# ESP32_D1_Mini_Breakout.net
KiCad netlist of a schematic drawn in EAGLE
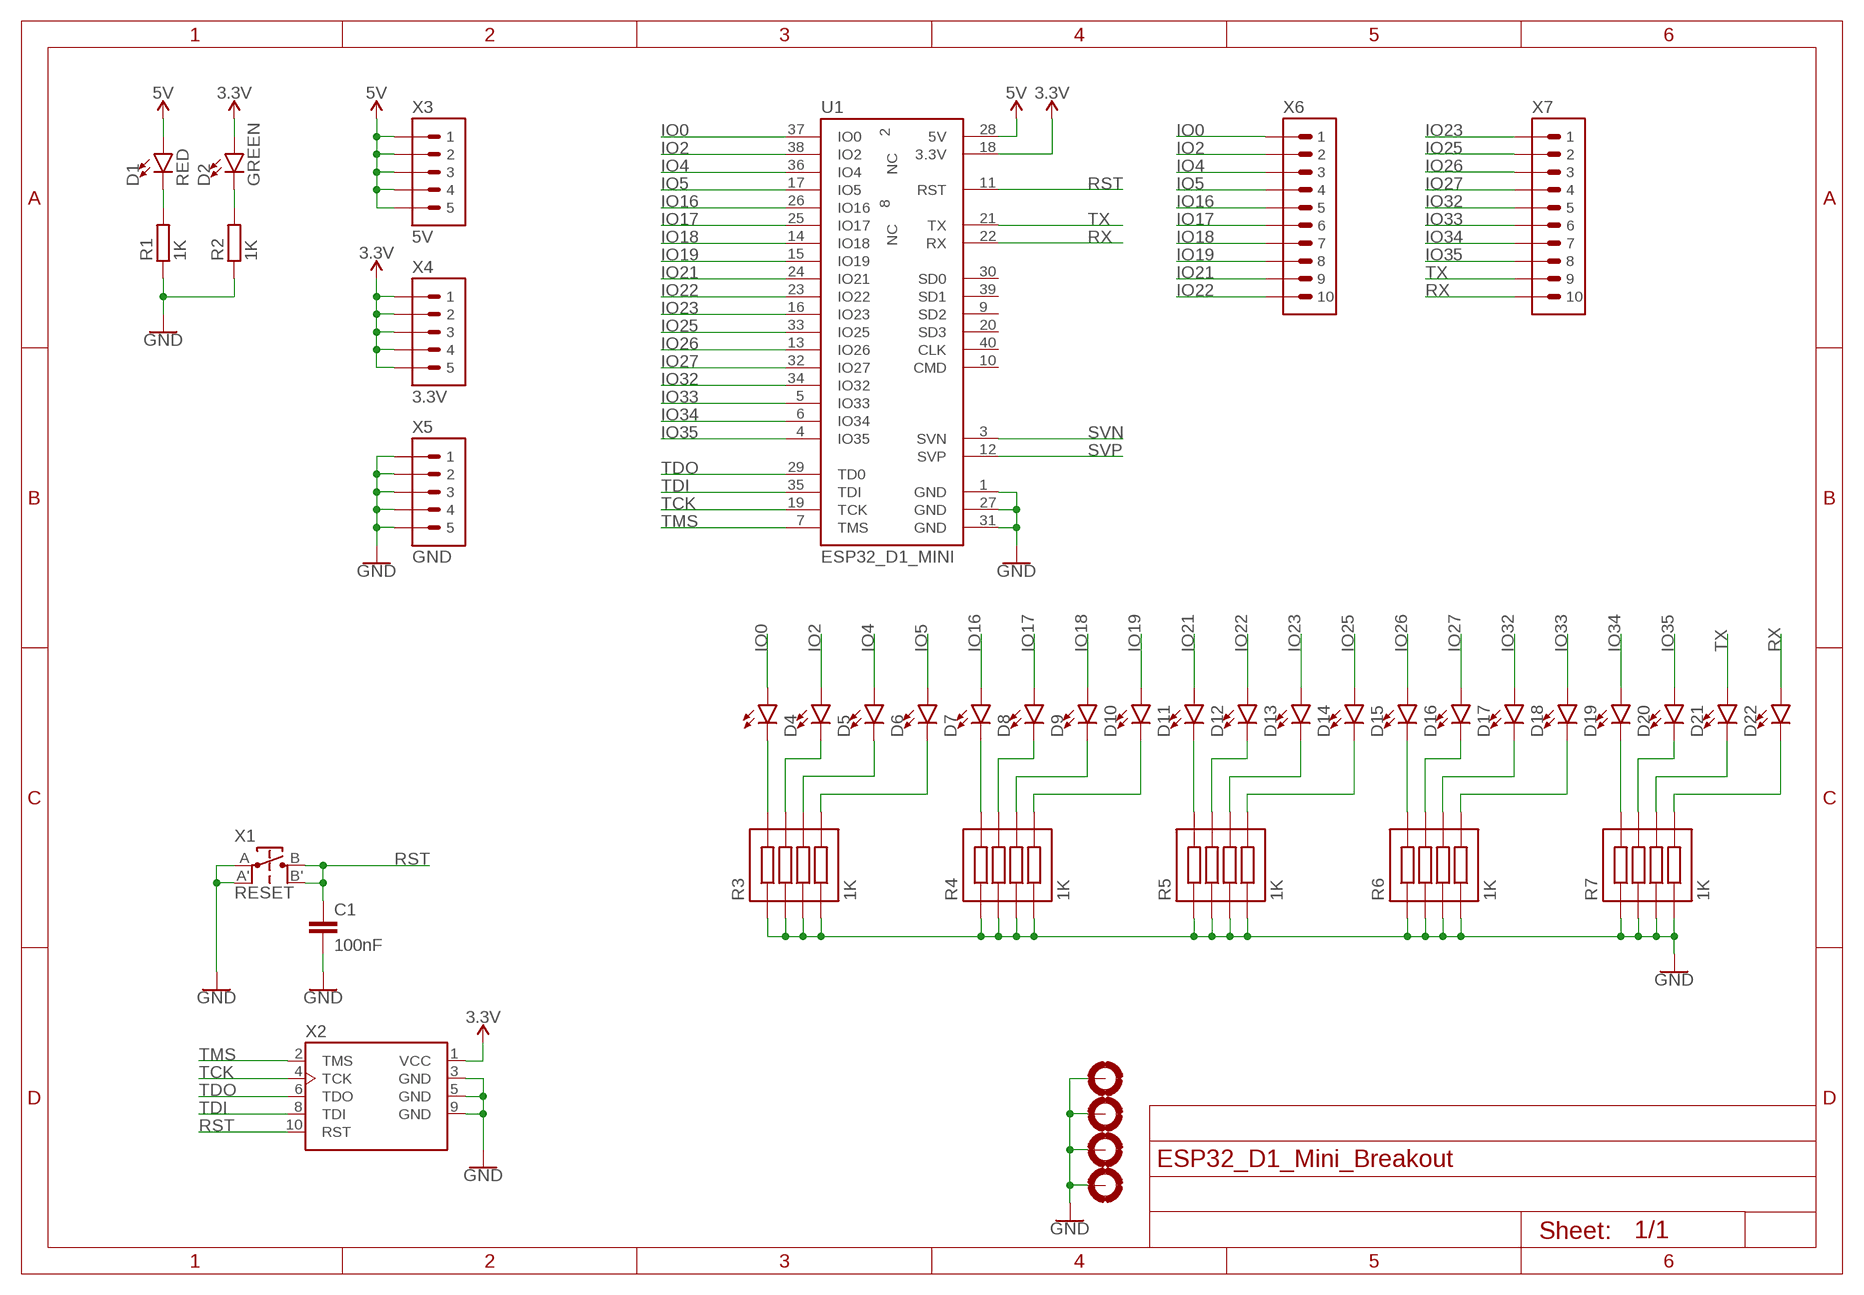
[diagram p0: schematic, sheet 1]

(export (version "E")
  (design (tool "Eeschema 10.0.6"))
  (components
    (comp (ref "C1")
      (value "100nF")
      (footprint "eagle-import:C0603")
      (libsource (lib "eagle-import") (part "CAPC0603"))
    )
    (comp (ref "D1")
      (value "RED")
      (footprint "eagle-import:LED0603")
      (libsource (lib "eagle-import") (part "LED0603"))
    )
    (comp (ref "D2")
      (value "GREEN")
      (footprint "eagle-import:LED0603")
      (libsource (lib "eagle-import") (part "LED0603"))
    )
    (comp (ref "D3")
      (value "LED0603")
      (footprint "eagle-import:LED0603")
      (libsource (lib "eagle-import") (part "LED0603"))
    )
    (comp (ref "D4")
      (value "LED0603")
      (footprint "eagle-import:LED0603")
      (libsource (lib "eagle-import") (part "LED0603"))
    )
    (comp (ref "D5")
      (value "LED0603")
      (footprint "eagle-import:LED0603")
      (libsource (lib "eagle-import") (part "LED0603"))
    )
    (comp (ref "D6")
      (value "LED0603")
      (footprint "eagle-import:LED0603")
      (libsource (lib "eagle-import") (part "LED0603"))
    )
    (comp (ref "D7")
      (value "LED0603")
      (footprint "eagle-import:LED0603")
      (libsource (lib "eagle-import") (part "LED0603"))
    )
    (comp (ref "D8")
      (value "LED0603")
      (footprint "eagle-import:LED0603")
      (libsource (lib "eagle-import") (part "LED0603"))
    )
    (comp (ref "D9")
      (value "LED0603")
      (footprint "eagle-import:LED0603")
      (libsource (lib "eagle-import") (part "LED0603"))
    )
    (comp (ref "D10")
      (value "LED0603")
      (footprint "eagle-import:LED0603")
      (libsource (lib "eagle-import") (part "LED0603"))
    )
    (comp (ref "D11")
      (value "LED0603")
      (footprint "eagle-import:LED0603")
      (libsource (lib "eagle-import") (part "LED0603"))
    )
    (comp (ref "D12")
      (value "LED0603")
      (footprint "eagle-import:LED0603")
      (libsource (lib "eagle-import") (part "LED0603"))
    )
    (comp (ref "D13")
      (value "LED0603")
      (footprint "eagle-import:LED0603")
      (libsource (lib "eagle-import") (part "LED0603"))
    )
    (comp (ref "D14")
      (value "LED0603")
      (footprint "eagle-import:LED0603")
      (libsource (lib "eagle-import") (part "LED0603"))
    )
    (comp (ref "D15")
      (value "LED0603")
      (footprint "eagle-import:LED0603")
      (libsource (lib "eagle-import") (part "LED0603"))
    )
    (comp (ref "D16")
      (value "LED0603")
      (footprint "eagle-import:LED0603")
      (libsource (lib "eagle-import") (part "LED0603"))
    )
    (comp (ref "D17")
      (value "LED0603")
      (footprint "eagle-import:LED0603")
      (libsource (lib "eagle-import") (part "LED0603"))
    )
    (comp (ref "D18")
      (value "LED0603")
      (footprint "eagle-import:LED0603")
      (libsource (lib "eagle-import") (part "LED0603"))
    )
    (comp (ref "D19")
      (value "LED0603")
      (footprint "eagle-import:LED0603")
      (libsource (lib "eagle-import") (part "LED0603"))
    )
    (comp (ref "D20")
      (value "LED0603")
      (footprint "eagle-import:LED0603")
      (libsource (lib "eagle-import") (part "LED0603"))
    )
    (comp (ref "D21")
      (value "LED0603")
      (footprint "eagle-import:LED0603")
      (libsource (lib "eagle-import") (part "LED0603"))
    )
    (comp (ref "D22")
      (value "LED0603")
      (footprint "eagle-import:LED0603")
      (libsource (lib "eagle-import") (part "LED0603"))
    )
    (comp (ref "H1")
      (value "MOUNTHOLE-PAD3.2")
      (footprint "eagle-import:3.2-PAD")
      (libsource (lib "eagle-import") (part "MOUNTHOLE-PAD3.2"))
    )
    (comp (ref "H2")
      (value "MOUNTHOLE-PAD3.2")
      (footprint "eagle-import:3.2-PAD")
      (libsource (lib "eagle-import") (part "MOUNTHOLE-PAD3.2"))
    )
    (comp (ref "H3")
      (value "MOUNTHOLE-PAD3.2")
      (footprint "eagle-import:3.2-PAD")
      (libsource (lib "eagle-import") (part "MOUNTHOLE-PAD3.2"))
    )
    (comp (ref "H4")
      (value "MOUNTHOLE-PAD3.2")
      (footprint "eagle-import:3.2-PAD")
      (libsource (lib "eagle-import") (part "MOUNTHOLE-PAD3.2"))
    )
    (comp (ref "R1")
      (value "1K")
      (footprint "eagle-import:R0603")
      (libsource (lib "eagle-import") (part "RESISTOR0603"))
    )
    (comp (ref "R2")
      (value "1K")
      (footprint "eagle-import:R0603")
      (libsource (lib "eagle-import") (part "RESISTOR0603"))
    )
    (comp (ref "R3")
      (value "1K")
      (footprint "eagle-import:RX4_1206")
      (libsource (lib "eagle-import") (part "RESISTOR-ARRAY-X41206"))
    )
    (comp (ref "R4")
      (value "1K")
      (footprint "eagle-import:RX4_1206")
      (libsource (lib "eagle-import") (part "RESISTOR-ARRAY-X41206"))
    )
    (comp (ref "R5")
      (value "1K")
      (footprint "eagle-import:RX4_1206")
      (libsource (lib "eagle-import") (part "RESISTOR-ARRAY-X41206"))
    )
    (comp (ref "R6")
      (value "1K")
      (footprint "eagle-import:RX4_1206")
      (libsource (lib "eagle-import") (part "RESISTOR-ARRAY-X41206"))
    )
    (comp (ref "R7")
      (value "1K")
      (footprint "eagle-import:RX4_1206")
      (libsource (lib "eagle-import") (part "RESISTOR-ARRAY-X41206"))
    )
    (comp (ref "U1")
      (value "ESP32_D1_MINI")
      (footprint "eagle-import:WEMOS_ESP32_D1_MINI")
      (libsource (lib "eagle-import") (part "WEMOS_ESP32_D1_MINI"))
    )
    (comp (ref "X1")
      (value "RESET")
      (footprint "eagle-import:TACT-SWITCH-EVQ")
      (libsource (lib "eagle-import") (part "TACT-SWITCHEVQ"))
    )
    (comp (ref "X2")
      (value "ESP32-JTAGTH")
      (footprint "eagle-import:2X05-1.27-SWD")
      (libsource (lib "eagle-import") (part "ESP32-JTAGTH"))
    )
    (comp (ref "X3")
      (value "5V")
      (footprint "eagle-import:1X05-2.54")
      (libsource (lib "eagle-import") (part "HEADER-1X05-2.54"))
    )
    (comp (ref "X4")
      (value "3.3V")
      (footprint "eagle-import:1X05-2.54")
      (libsource (lib "eagle-import") (part "HEADER-1X05-2.54"))
    )
    (comp (ref "X5")
      (value "GND")
      (footprint "eagle-import:1X05-2.54")
      (libsource (lib "eagle-import") (part "HEADER-1X05-2.54"))
    )
    (comp (ref "X6")
      (value "HEADER-1X10-2.54")
      (footprint "eagle-import:1X10-2.54")
      (libsource (lib "eagle-import") (part "HEADER-1X10-2.54"))
    )
    (comp (ref "X7")
      (value "HEADER-1X10-2.54")
      (footprint "eagle-import:1X10-2.54")
      (libsource (lib "eagle-import") (part "HEADER-1X10-2.54"))
    )
  )
  (nets
    (net (code "1") (name "/IO0") (class "Default")
      (node (ref "D3") (pin "A") (pinfunction "A_A") (pintype "passive"))
      (node (ref "U1") (pin "37") (pinfunction "IO0_37") (pintype "bidirectional"))
      (node (ref "X6") (pin "1") (pinfunction "1_1") (pintype "passive"))
    )
    (net (code "2") (name "/IO2") (class "Default")
      (node (ref "D4") (pin "A") (pinfunction "A_A") (pintype "passive"))
      (node (ref "U1") (pin "38") (pinfunction "IO2_38") (pintype "bidirectional"))
      (node (ref "X6") (pin "2") (pinfunction "2_2") (pintype "passive"))
    )
    (net (code "3") (name "/IO4") (class "Default")
      (node (ref "D5") (pin "A") (pinfunction "A_A") (pintype "passive"))
      (node (ref "U1") (pin "36") (pinfunction "IO4_36") (pintype "bidirectional"))
      (node (ref "X6") (pin "3") (pinfunction "3_3") (pintype "passive"))
    )
    (net (code "4") (name "/IO5") (class "Default")
      (node (ref "D6") (pin "A") (pinfunction "A_A") (pintype "passive"))
      (node (ref "U1") (pin "17") (pinfunction "IO5_17") (pintype "bidirectional"))
      (node (ref "X6") (pin "4") (pinfunction "4_4") (pintype "passive"))
    )
    (net (code "5") (name "/IO16") (class "Default")
      (node (ref "D7") (pin "A") (pinfunction "A_A") (pintype "passive"))
      (node (ref "U1") (pin "26") (pinfunction "IO16_26") (pintype "bidirectional"))
      (node (ref "X6") (pin "5") (pinfunction "5_5") (pintype "passive"))
    )
    (net (code "6") (name "/IO17") (class "Default")
      (node (ref "D8") (pin "A") (pinfunction "A_A") (pintype "passive"))
      (node (ref "U1") (pin "25") (pinfunction "IO17_25") (pintype "bidirectional"))
      (node (ref "X6") (pin "6") (pinfunction "6_6") (pintype "passive"))
    )
    (net (code "7") (name "/IO18") (class "Default")
      (node (ref "D9") (pin "A") (pinfunction "A_A") (pintype "passive"))
      (node (ref "U1") (pin "14") (pinfunction "IO18_14") (pintype "bidirectional"))
      (node (ref "X6") (pin "7") (pinfunction "7_7") (pintype "passive"))
    )
    (net (code "8") (name "/IO19") (class "Default")
      (node (ref "D10") (pin "A") (pinfunction "A_A") (pintype "passive"))
      (node (ref "U1") (pin "15") (pinfunction "IO19_15") (pintype "bidirectional"))
      (node (ref "X6") (pin "8") (pinfunction "8_8") (pintype "bidirectional"))
    )
    (net (code "9") (name "/IO21") (class "Default")
      (node (ref "D11") (pin "A") (pinfunction "A_A") (pintype "passive"))
      (node (ref "U1") (pin "24") (pinfunction "IO21_24") (pintype "bidirectional"))
      (node (ref "X6") (pin "9") (pinfunction "9_9") (pintype "bidirectional"))
    )
    (net (code "10") (name "/IO22") (class "Default")
      (node (ref "D12") (pin "A") (pinfunction "A_A") (pintype "passive"))
      (node (ref "U1") (pin "23") (pinfunction "IO22_23") (pintype "bidirectional"))
      (node (ref "X6") (pin "10") (pinfunction "10_10") (pintype "bidirectional"))
    )
    (net (code "11") (name "/IO23") (class "Default")
      (node (ref "D13") (pin "A") (pinfunction "A_A") (pintype "passive"))
      (node (ref "U1") (pin "16") (pinfunction "IO23_16") (pintype "bidirectional"))
      (node (ref "X7") (pin "1") (pinfunction "1_1") (pintype "passive"))
    )
    (net (code "12") (name "/IO25") (class "Default")
      (node (ref "D14") (pin "A") (pinfunction "A_A") (pintype "passive"))
      (node (ref "U1") (pin "33") (pinfunction "IO25_33") (pintype "bidirectional"))
      (node (ref "X7") (pin "2") (pinfunction "2_2") (pintype "passive"))
    )
    (net (code "13") (name "/IO26") (class "Default")
      (node (ref "D15") (pin "A") (pinfunction "A_A") (pintype "passive"))
      (node (ref "U1") (pin "13") (pinfunction "IO26_13") (pintype "bidirectional"))
      (node (ref "X7") (pin "3") (pinfunction "3_3") (pintype "passive"))
    )
    (net (code "14") (name "/IO27") (class "Default")
      (node (ref "D16") (pin "A") (pinfunction "A_A") (pintype "passive"))
      (node (ref "U1") (pin "32") (pinfunction "IO27_32") (pintype "bidirectional"))
      (node (ref "X7") (pin "4") (pinfunction "4_4") (pintype "passive"))
    )
    (net (code "15") (name "/IO32") (class "Default")
      (node (ref "D17") (pin "A") (pinfunction "A_A") (pintype "passive"))
      (node (ref "U1") (pin "34") (pinfunction "IO32_34") (pintype "bidirectional"))
      (node (ref "X7") (pin "5") (pinfunction "5_5") (pintype "passive"))
    )
    (net (code "16") (name "/IO33") (class "Default")
      (node (ref "D18") (pin "A") (pinfunction "A_A") (pintype "passive"))
      (node (ref "U1") (pin "5") (pinfunction "IO33_5") (pintype "bidirectional"))
      (node (ref "X7") (pin "6") (pinfunction "6_6") (pintype "passive"))
    )
    (net (code "17") (name "/IO34") (class "Default")
      (node (ref "D19") (pin "A") (pinfunction "A_A") (pintype "passive"))
      (node (ref "U1") (pin "6") (pinfunction "IO34_6") (pintype "bidirectional"))
      (node (ref "X7") (pin "7") (pinfunction "7_7") (pintype "passive"))
    )
    (net (code "18") (name "/IO35") (class "Default")
      (node (ref "D20") (pin "A") (pinfunction "A_A") (pintype "passive"))
      (node (ref "U1") (pin "4") (pinfunction "IO35_4") (pintype "bidirectional"))
      (node (ref "X7") (pin "8") (pinfunction "8_8") (pintype "bidirectional"))
    )
    (net (code "19") (name "/RST") (class "Default")
      (node (ref "C1") (pin "1") (pinfunction "1_1") (pintype "passive"))
      (node (ref "U1") (pin "11") (pinfunction "RST_11") (pintype "bidirectional"))
      (node (ref "X1") (pin "B") (pinfunction "B_B") (pintype "bidirectional"))
      (node (ref "X1") (pin "B'") (pinfunction "B'_B'") (pintype "bidirectional"))
      (node (ref "X2") (pin "10") (pinfunction "RST_10") (pintype "output"))
    )
    (net (code "20") (name "/RX") (class "Default")
      (node (ref "D22") (pin "A") (pinfunction "A_A") (pintype "passive"))
      (node (ref "U1") (pin "22") (pinfunction "RX_22") (pintype "bidirectional"))
      (node (ref "X7") (pin "10") (pinfunction "10_10") (pintype "bidirectional"))
    )
    (net (code "21") (name "/SVN") (class "Default")
      (node (ref "U1") (pin "3") (pinfunction "SVN_3") (pintype "bidirectional"))
    )
    (net (code "22") (name "/SVP") (class "Default")
      (node (ref "U1") (pin "12") (pinfunction "SVP_12") (pintype "bidirectional"))
    )
    (net (code "23") (name "/TCK") (class "Default")
      (node (ref "U1") (pin "19") (pinfunction "TCK_19") (pintype "bidirectional"))
      (node (ref "X2") (pin "4") (pinfunction "TCK_4") (pintype "output"))
    )
    (net (code "24") (name "/TDI") (class "Default")
      (node (ref "U1") (pin "35") (pinfunction "TDI_35") (pintype "bidirectional"))
      (node (ref "X2") (pin "8") (pinfunction "TDI_8") (pintype "input"))
    )
    (net (code "25") (name "/TDO") (class "Default")
      (node (ref "U1") (pin "29") (pinfunction "TD0_29") (pintype "bidirectional"))
      (node (ref "X2") (pin "6") (pinfunction "TDO_6") (pintype "output"))
    )
    (net (code "26") (name "/TMS") (class "Default")
      (node (ref "U1") (pin "7") (pinfunction "TMS_7") (pintype "bidirectional"))
      (node (ref "X2") (pin "2") (pinfunction "TMS_2") (pintype "output"))
    )
    (net (code "27") (name "/TX") (class "Default")
      (node (ref "D21") (pin "A") (pinfunction "A_A") (pintype "passive"))
      (node (ref "U1") (pin "21") (pinfunction "TX_21") (pintype "bidirectional"))
      (node (ref "X7") (pin "9") (pinfunction "9_9") (pintype "bidirectional"))
    )
    (net (code "28") (name "3.3V") (class "Default")
      (node (ref "D2") (pin "A") (pinfunction "A_A") (pintype "passive"))
      (node (ref "U1") (pin "18") (pinfunction "3.3V_18") (pintype "bidirectional"))
      (node (ref "X2") (pin "1") (pinfunction "VCC_1") (pintype "power_in"))
      (node (ref "X4") (pin "1") (pinfunction "1_1") (pintype "passive"))
      (node (ref "X4") (pin "2") (pinfunction "2_2") (pintype "passive"))
      (node (ref "X4") (pin "3") (pinfunction "3_3") (pintype "passive"))
      (node (ref "X4") (pin "4") (pinfunction "4_4") (pintype "passive"))
      (node (ref "X4") (pin "5") (pinfunction "5_5") (pintype "passive"))
    )
    (net (code "29") (name "5V") (class "Default")
      (node (ref "D1") (pin "A") (pinfunction "A_A") (pintype "passive"))
      (node (ref "U1") (pin "28") (pinfunction "5V_28") (pintype "bidirectional"))
      (node (ref "X3") (pin "1") (pinfunction "1_1") (pintype "passive"))
      (node (ref "X3") (pin "2") (pinfunction "2_2") (pintype "passive"))
      (node (ref "X3") (pin "3") (pinfunction "3_3") (pintype "passive"))
      (node (ref "X3") (pin "4") (pinfunction "4_4") (pintype "passive"))
      (node (ref "X3") (pin "5") (pinfunction "5_5") (pintype "passive"))
    )
    (net (code "30") (name "GND") (class "Default")
      (node (ref "C1") (pin "2") (pinfunction "2_2") (pintype "passive"))
      (node (ref "H1") (pin "B3,2") (pinfunction "MOUNT_B3,2") (pintype "passive"))
      (node (ref "H2") (pin "B3,2") (pinfunction "MOUNT_B3,2") (pintype "passive"))
      (node (ref "H3") (pin "B3,2") (pinfunction "MOUNT_B3,2") (pintype "passive"))
      (node (ref "H4") (pin "B3,2") (pinfunction "MOUNT_B3,2") (pintype "passive"))
      (node (ref "R1") (pin "1") (pinfunction "1_1") (pintype "passive"))
      (node (ref "R2") (pin "1") (pinfunction "1_1") (pintype "passive"))
      (node (ref "R3") (pin "1") (pinfunction "1_1") (pintype "passive"))
      (node (ref "R3") (pin "3") (pinfunction "3_3") (pintype "passive"))
      (node (ref "R3") (pin "5") (pinfunction "5_5") (pintype "passive"))
      (node (ref "R3") (pin "7") (pinfunction "7_7") (pintype "passive"))
      (node (ref "R4") (pin "1") (pinfunction "1_1") (pintype "passive"))
      (node (ref "R4") (pin "3") (pinfunction "3_3") (pintype "passive"))
      (node (ref "R4") (pin "5") (pinfunction "5_5") (pintype "passive"))
      (node (ref "R4") (pin "7") (pinfunction "7_7") (pintype "passive"))
      (node (ref "R5") (pin "1") (pinfunction "1_1") (pintype "passive"))
      (node (ref "R5") (pin "3") (pinfunction "3_3") (pintype "passive"))
      (node (ref "R5") (pin "5") (pinfunction "5_5") (pintype "passive"))
      (node (ref "R5") (pin "7") (pinfunction "7_7") (pintype "passive"))
      (node (ref "R6") (pin "1") (pinfunction "1_1") (pintype "passive"))
      (node (ref "R6") (pin "3") (pinfunction "3_3") (pintype "passive"))
      (node (ref "R6") (pin "5") (pinfunction "5_5") (pintype "passive"))
      (node (ref "R6") (pin "7") (pinfunction "7_7") (pintype "passive"))
      (node (ref "R7") (pin "1") (pinfunction "1_1") (pintype "passive"))
      (node (ref "R7") (pin "3") (pinfunction "3_3") (pintype "passive"))
      (node (ref "R7") (pin "5") (pinfunction "5_5") (pintype "passive"))
      (node (ref "R7") (pin "7") (pinfunction "7_7") (pintype "passive"))
      (node (ref "U1") (pin "1") (pinfunction "GND_1") (pintype "bidirectional"))
      (node (ref "U1") (pin "27") (pinfunction "GND_27") (pintype "bidirectional"))
      (node (ref "U1") (pin "31") (pinfunction "GND_31") (pintype "bidirectional"))
      (node (ref "X1") (pin "A") (pinfunction "A_A") (pintype "bidirectional"))
      (node (ref "X1") (pin "A'") (pinfunction "A'_A'") (pintype "bidirectional"))
      (node (ref "X2") (pin "3") (pinfunction "GND_3") (pintype "power_in"))
      (node (ref "X2") (pin "5") (pinfunction "GND_5") (pintype "power_in"))
      (node (ref "X2") (pin "9") (pinfunction "GND_9") (pintype "power_in"))
      (node (ref "X5") (pin "1") (pinfunction "1_1") (pintype "passive"))
      (node (ref "X5") (pin "2") (pinfunction "2_2") (pintype "passive"))
      (node (ref "X5") (pin "3") (pinfunction "3_3") (pintype "passive"))
      (node (ref "X5") (pin "4") (pinfunction "4_4") (pintype "passive"))
      (node (ref "X5") (pin "5") (pinfunction "5_5") (pintype "passive"))
    )
    (net (code "31") (name "Net-(D1-PadC)") (class "Default")
      (node (ref "D1") (pin "C") (pinfunction "C_C") (pintype "passive"))
      (node (ref "R1") (pin "2") (pinfunction "2_2") (pintype "passive"))
    )
    (net (code "32") (name "Net-(D2-PadC)") (class "Default")
      (node (ref "D2") (pin "C") (pinfunction "C_C") (pintype "passive"))
      (node (ref "R2") (pin "2") (pinfunction "2_2") (pintype "passive"))
    )
    (net (code "33") (name "Net-(D3-PadC)") (class "Default")
      (node (ref "D3") (pin "C") (pinfunction "C_C") (pintype "passive"))
      (node (ref "R3") (pin "2") (pinfunction "2_2") (pintype "passive"))
    )
    (net (code "34") (name "Net-(D4-PadC)") (class "Default")
      (node (ref "D4") (pin "C") (pinfunction "C_C") (pintype "passive"))
      (node (ref "R3") (pin "4") (pinfunction "4_4") (pintype "passive"))
    )
    (net (code "35") (name "Net-(D5-PadC)") (class "Default")
      (node (ref "D5") (pin "C") (pinfunction "C_C") (pintype "passive"))
      (node (ref "R3") (pin "6") (pinfunction "6_6") (pintype "passive"))
    )
    (net (code "36") (name "Net-(D6-PadC)") (class "Default")
      (node (ref "D6") (pin "C") (pinfunction "C_C") (pintype "passive"))
      (node (ref "R3") (pin "8") (pinfunction "8_8") (pintype "passive"))
    )
    (net (code "37") (name "Net-(D7-PadC)") (class "Default")
      (node (ref "D7") (pin "C") (pinfunction "C_C") (pintype "passive"))
      (node (ref "R4") (pin "2") (pinfunction "2_2") (pintype "passive"))
    )
    (net (code "38") (name "Net-(D8-PadC)") (class "Default")
      (node (ref "D8") (pin "C") (pinfunction "C_C") (pintype "passive"))
      (node (ref "R4") (pin "4") (pinfunction "4_4") (pintype "passive"))
    )
    (net (code "39") (name "Net-(D9-PadC)") (class "Default")
      (node (ref "D9") (pin "C") (pinfunction "C_C") (pintype "passive"))
      (node (ref "R4") (pin "6") (pinfunction "6_6") (pintype "passive"))
    )
    (net (code "40") (name "Net-(D10-PadC)") (class "Default")
      (node (ref "D10") (pin "C") (pinfunction "C_C") (pintype "passive"))
      (node (ref "R4") (pin "8") (pinfunction "8_8") (pintype "passive"))
    )
    (net (code "41") (name "Net-(D11-PadC)") (class "Default")
      (node (ref "D11") (pin "C") (pinfunction "C_C") (pintype "passive"))
      (node (ref "R5") (pin "2") (pinfunction "2_2") (pintype "passive"))
    )
    (net (code "42") (name "Net-(D12-PadC)") (class "Default")
      (node (ref "D12") (pin "C") (pinfunction "C_C") (pintype "passive"))
      (node (ref "R5") (pin "4") (pinfunction "4_4") (pintype "passive"))
    )
    (net (code "43") (name "Net-(D13-PadC)") (class "Default")
      (node (ref "D13") (pin "C") (pinfunction "C_C") (pintype "passive"))
      (node (ref "R5") (pin "6") (pinfunction "6_6") (pintype "passive"))
    )
    (net (code "44") (name "Net-(D14-PadC)") (class "Default")
      (node (ref "D14") (pin "C") (pinfunction "C_C") (pintype "passive"))
      (node (ref "R5") (pin "8") (pinfunction "8_8") (pintype "passive"))
    )
    (net (code "45") (name "Net-(D15-PadC)") (class "Default")
      (node (ref "D15") (pin "C") (pinfunction "C_C") (pintype "passive"))
      (node (ref "R6") (pin "2") (pinfunction "2_2") (pintype "passive"))
    )
    (net (code "46") (name "Net-(D16-PadC)") (class "Default")
      (node (ref "D16") (pin "C") (pinfunction "C_C") (pintype "passive"))
      (node (ref "R6") (pin "4") (pinfunction "4_4") (pintype "passive"))
    )
    (net (code "47") (name "Net-(D17-PadC)") (class "Default")
      (node (ref "D17") (pin "C") (pinfunction "C_C") (pintype "passive"))
      (node (ref "R6") (pin "6") (pinfunction "6_6") (pintype "passive"))
    )
    (net (code "48") (name "Net-(D18-PadC)") (class "Default")
      (node (ref "D18") (pin "C") (pinfunction "C_C") (pintype "passive"))
      (node (ref "R6") (pin "8") (pinfunction "8_8") (pintype "passive"))
    )
    (net (code "49") (name "Net-(D19-PadC)") (class "Default")
      (node (ref "D19") (pin "C") (pinfunction "C_C") (pintype "passive"))
      (node (ref "R7") (pin "2") (pinfunction "2_2") (pintype "passive"))
    )
    (net (code "50") (name "Net-(D20-PadC)") (class "Default")
      (node (ref "D20") (pin "C") (pinfunction "C_C") (pintype "passive"))
      (node (ref "R7") (pin "4") (pinfunction "4_4") (pintype "passive"))
    )
    (net (code "51") (name "Net-(D21-PadC)") (class "Default")
      (node (ref "D21") (pin "C") (pinfunction "C_C") (pintype "passive"))
      (node (ref "R7") (pin "6") (pinfunction "6_6") (pintype "passive"))
    )
    (net (code "52") (name "Net-(D22-PadC)") (class "Default")
      (node (ref "D22") (pin "C") (pinfunction "C_C") (pintype "passive"))
      (node (ref "R7") (pin "8") (pinfunction "8_8") (pintype "passive"))
    )
    (net (code "53") (name "unconnected-(U1-CLK-Pad40)") (class "Default")
      (node (ref "U1") (pin "40") (pinfunction "CLK_40") (pintype "bidirectional"))
    )
    (net (code "54") (name "unconnected-(U1-CMD-Pad10)") (class "Default")
      (node (ref "U1") (pin "10") (pinfunction "CMD_10") (pintype "bidirectional"))
    )
    (net (code "55") (name "unconnected-(U1-NC-Pad2)") (class "Default")
      (node (ref "U1") (pin "2") (pinfunction "NC_2") (pintype "bidirectional"))
    )
    (net (code "56") (name "unconnected-(U1-NC-Pad8)") (class "Default")
      (node (ref "U1") (pin "8") (pinfunction "NC_8") (pintype "bidirectional"))
    )
    (net (code "57") (name "unconnected-(U1-SD0-Pad30)") (class "Default")
      (node (ref "U1") (pin "30") (pinfunction "SD0_30") (pintype "bidirectional"))
    )
    (net (code "58") (name "unconnected-(U1-SD1-Pad39)") (class "Default")
      (node (ref "U1") (pin "39") (pinfunction "SD1_39") (pintype "bidirectional"))
    )
    (net (code "59") (name "unconnected-(U1-SD2-Pad9)") (class "Default")
      (node (ref "U1") (pin "9") (pinfunction "SD2_9") (pintype "bidirectional"))
    )
    (net (code "60") (name "unconnected-(U1-SD3-Pad20)") (class "Default")
      (node (ref "U1") (pin "20") (pinfunction "SD3_20") (pintype "bidirectional"))
    )
  )
)
